# charlieplexing-8-led-schematic.net
KiCad netlist of a schematic drawn in EAGLE
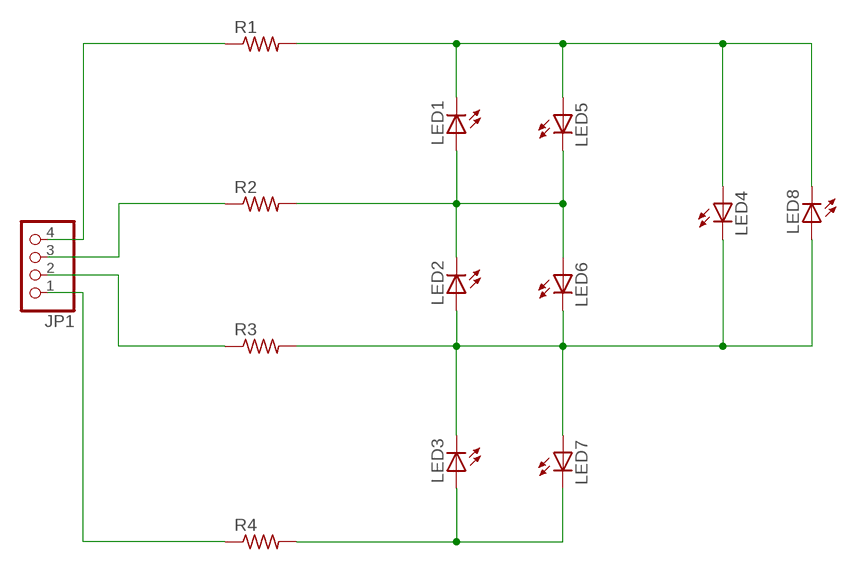
[diagram p0: schematic, sheet 1]

(export (version "E")
  (design (tool "Eeschema 10.0.6"))
  (components
    (comp (ref "JP1")
      (value "PINHD-1X4")
      (footprint "eagle-import:1X04")
      (libsource (lib "eagle-import") (part "PINHD-1X4"))
    )
    (comp (ref "LED1")
      (value "LED5MM")
      (footprint "eagle-import:LED5MM")
      (libsource (lib "eagle-import") (part "LED5MM"))
    )
    (comp (ref "LED2")
      (value "LED5MM")
      (footprint "eagle-import:LED5MM")
      (libsource (lib "eagle-import") (part "LED5MM"))
    )
    (comp (ref "LED3")
      (value "LED5MM")
      (footprint "eagle-import:LED5MM")
      (libsource (lib "eagle-import") (part "LED5MM"))
    )
    (comp (ref "LED4")
      (value "LED5MM")
      (footprint "eagle-import:LED5MM")
      (libsource (lib "eagle-import") (part "LED5MM"))
    )
    (comp (ref "LED5")
      (value "LED3MM")
      (footprint "eagle-import:LED3MM")
      (libsource (lib "eagle-import") (part "LED3MM"))
    )
    (comp (ref "LED6")
      (value "LED3MM")
      (footprint "eagle-import:LED3MM")
      (libsource (lib "eagle-import") (part "LED3MM"))
    )
    (comp (ref "LED7")
      (value "LED3MM")
      (footprint "eagle-import:LED3MM")
      (libsource (lib "eagle-import") (part "LED3MM"))
    )
    (comp (ref "LED8")
      (value "LED3MM")
      (footprint "eagle-import:LED3MM")
      (libsource (lib "eagle-import") (part "LED3MM"))
    )
    (comp (ref "R1")
      (value "R-US_0207/10")
      (footprint "eagle-import:0207_10")
      (libsource (lib "eagle-import") (part "R-US_0207/10"))
    )
    (comp (ref "R2")
      (value "R-US_0207/10")
      (footprint "eagle-import:0207_10")
      (libsource (lib "eagle-import") (part "R-US_0207/10"))
    )
    (comp (ref "R3")
      (value "R-US_0207/10")
      (footprint "eagle-import:0207_10")
      (libsource (lib "eagle-import") (part "R-US_0207/10"))
    )
    (comp (ref "R4")
      (value "R-US_0207/10")
      (footprint "eagle-import:0207_10")
      (libsource (lib "eagle-import") (part "R-US_0207/10"))
    )
  )
  (nets
    (net (code "1") (name "Net-(JP1-Pad1)") (class "Default")
      (node (ref "JP1") (pin "1") (pinfunction "1_1") (pintype "passive"))
      (node (ref "R4") (pin "1") (pinfunction "1_1") (pintype "passive"))
    )
    (net (code "2") (name "Net-(JP1-Pad2)") (class "Default")
      (node (ref "JP1") (pin "2") (pinfunction "2_2") (pintype "passive"))
      (node (ref "R3") (pin "1") (pinfunction "1_1") (pintype "passive"))
    )
    (net (code "3") (name "Net-(JP1-Pad3)") (class "Default")
      (node (ref "JP1") (pin "3") (pinfunction "3_3") (pintype "passive"))
      (node (ref "R2") (pin "1") (pinfunction "1_1") (pintype "passive"))
    )
    (net (code "4") (name "Net-(JP1-Pad4)") (class "Default")
      (node (ref "JP1") (pin "4") (pinfunction "4_4") (pintype "passive"))
      (node (ref "R1") (pin "1") (pinfunction "1_1") (pintype "passive"))
    )
    (net (code "5") (name "Net-(LED1-C)") (class "Default")
      (node (ref "LED1") (pin "K") (pinfunction "C_K") (pintype "passive"))
      (node (ref "LED4") (pin "A") (pinfunction "A_A") (pintype "passive"))
      (node (ref "LED5") (pin "A") (pinfunction "A_A") (pintype "passive"))
      (node (ref "LED8") (pin "K") (pinfunction "C_K") (pintype "passive"))
      (node (ref "R1") (pin "2") (pinfunction "2_2") (pintype "passive"))
    )
    (net (code "6") (name "Net-(LED2-C)") (class "Default")
      (node (ref "LED1") (pin "A") (pinfunction "A_A") (pintype "passive"))
      (node (ref "LED2") (pin "K") (pinfunction "C_K") (pintype "passive"))
      (node (ref "LED5") (pin "K") (pinfunction "C_K") (pintype "passive"))
      (node (ref "LED6") (pin "A") (pinfunction "A_A") (pintype "passive"))
      (node (ref "R2") (pin "2") (pinfunction "2_2") (pintype "passive"))
    )
    (net (code "7") (name "Net-(LED3-C)") (class "Default")
      (node (ref "LED2") (pin "A") (pinfunction "A_A") (pintype "passive"))
      (node (ref "LED3") (pin "K") (pinfunction "C_K") (pintype "passive"))
      (node (ref "LED4") (pin "K") (pinfunction "C_K") (pintype "passive"))
      (node (ref "LED6") (pin "K") (pinfunction "C_K") (pintype "passive"))
      (node (ref "LED7") (pin "A") (pinfunction "A_A") (pintype "passive"))
      (node (ref "LED8") (pin "A") (pinfunction "A_A") (pintype "passive"))
      (node (ref "R3") (pin "2") (pinfunction "2_2") (pintype "passive"))
    )
    (net (code "8") (name "Net-(LED7-C)") (class "Default")
      (node (ref "LED3") (pin "A") (pinfunction "A_A") (pintype "passive"))
      (node (ref "LED7") (pin "K") (pinfunction "C_K") (pintype "passive"))
      (node (ref "R4") (pin "2") (pinfunction "2_2") (pintype "passive"))
    )
  )
)
